# SiLabs2TC.net
KiCad netlist of a schematic drawn in EAGLE
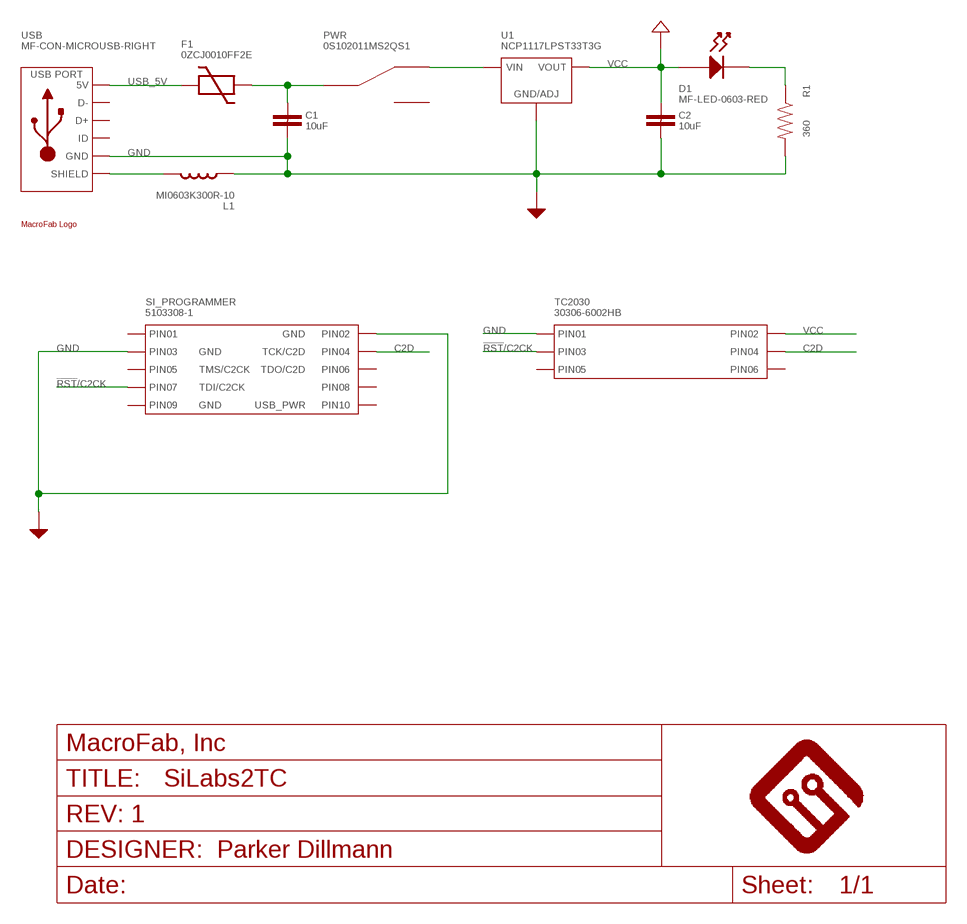
[diagram p0: schematic, sheet 1]

(export (version "E")
  (design (tool "Eeschema 10.0.6"))
  (components
    (comp (ref "C1")
      (value "10uF")
      (footprint "eagle-import:1206")
      (libsource (lib "eagle-import") (part "CAPACITOR_NON_POLAR_1206"))
    )
    (comp (ref "C2")
      (value "10uF")
      (footprint "eagle-import:1206")
      (libsource (lib "eagle-import") (part "CAPACITOR_NON_POLAR_1206"))
    )
    (comp (ref "D1")
      (value "MF-LED-0603-RED")
      (footprint "eagle-import:LED0805")
      (libsource (lib "eagle-import") (part "LED_SINGLE_0805"))
    )
    (comp (ref "F1")
      (value "0ZCJ0010FF2E")
      (footprint "eagle-import:1206")
      (libsource (lib "eagle-import") (part "PTC_FUSE_1206"))
    )
    (comp (ref "FRAME1")
      (value "MF_FRAMEDEFAULT")
      (footprint "eagle-import:MF_FRAME_DEFAULT")
      (fields (field (name "DNAME") "Parker Dillmann") (field (name "REVNUM") "REV: 1"))
      (libsource (lib "eagle-import") (part "MF_FRAMEDEFAULT"))
    )
    (comp (ref "L1")
      (value "MI0603K300R-10")
      (footprint "eagle-import:L0603")
      (libsource (lib "eagle-import") (part "INDUCTOR_0603"))
    )
    (comp (ref "PWR")
      (value "0S102011MS2QS1")
      (footprint "eagle-import:0S102011MS2QS1")
      (libsource (lib "eagle-import") (part "SPDT_0S102011MS2QS1"))
    )
    (comp (ref "R1")
      (value "360")
      (footprint "eagle-import:R0805")
      (libsource (lib "eagle-import") (part "RESISTOR_0805"))
    )
    (comp (ref "SI_PROGRAMMER")
      (value "5103308-1")
      (footprint "eagle-import:5103308-1")
      (fields
        (field (name "LABEL02") "GND")
        (field (name "LABEL03") "GND")
        (field (name "LABEL04") "TCK/C2D")
        (field (name "LABEL05") "TMS/C2CK")
        (field (name "LABEL06") "TDO/C2D")
        (field (name "LABEL07") "TDI/C2CK")
        (field (name "LABEL09") "GND")
        (field (name "LABEL10") "USB_PWR")
      )
      (libsource (lib "eagle-import") (part "CON_02X05_5103308-1"))
    )
    (comp (ref "TC2030")
      (value "30306-6002HB")
      (footprint "eagle-import:30306-6002HB")
      (libsource (lib "eagle-import") (part "CON_02X03_30306-6002HB"))
    )
    (comp (ref "U$3")
      (value "MF_LOGOLOGO_MEDIUM")
      (footprint "eagle-import:MF_LOGO_MEDIUM")
      (libsource (lib "eagle-import") (part "MF_LOGOLOGO_MEDIUM"))
    )
    (comp (ref "U1")
      (value "NCP1117LPST33T3G")
      (footprint "eagle-import:SOT-223-3")
      (libsource (lib "eagle-import") (part "NCP1117LPST33T3G"))
    )
    (comp (ref "USB")
      (value "MF-CON-MICROUSB-RIGHT")
      (footprint "eagle-import:MICROUSB-RIGHT")
      (libsource (lib "eagle-import") (part "USB_MICRO_RIGHT"))
    )
  )
  (nets
    (net (code "1") (name "/C2D") (class "Default")
      (node (ref "SI_PROGRAMMER") (pin "4") (pinfunction "PIN4_4") (pintype "bidirectional"))
      (node (ref "TC2030") (pin "4") (pinfunction "PIN4_4") (pintype "bidirectional"))
    )
    (net (code "2") (name "/USB_5V") (class "Default")
      (node (ref "F1") (pin "1") (pinfunction "P$1_1") (pintype "bidirectional"))
      (node (ref "USB") (pin "1") (pinfunction "5V_1") (pintype "power_in"))
    )
    (net (code "3") (name "/~{RST}{slash}C2CK") (class "Default")
      (node (ref "SI_PROGRAMMER") (pin "7") (pinfunction "PIN7_7") (pintype "bidirectional"))
      (node (ref "TC2030") (pin "3") (pinfunction "PIN3_3") (pintype "bidirectional"))
    )
    (net (code "4") (name "GND_RAIL") (class "Default")
      (node (ref "C1") (pin "2") (pinfunction "2_2") (pintype "passive"))
      (node (ref "C2") (pin "2") (pinfunction "2_2") (pintype "passive"))
      (node (ref "L1") (pin "P$1") (pinfunction "P$1_P$1") (pintype "passive"))
      (node (ref "R1") (pin "P$2") (pinfunction "P$2_P$2") (pintype "passive"))
      (node (ref "SI_PROGRAMMER") (pin "2") (pinfunction "PIN2_2") (pintype "bidirectional"))
      (node (ref "SI_PROGRAMMER") (pin "3") (pinfunction "PIN3_3") (pintype "bidirectional"))
      (node (ref "TC2030") (pin "1") (pinfunction "PIN1_1") (pintype "bidirectional"))
      (node (ref "U1") (pin "P$2") (pinfunction "GND/ADJ_P$2") (pintype "bidirectional"))
      (node (ref "USB") (pin "5") (pinfunction "GND_5") (pintype "power_in"))
    )
    (net (code "5") (name "Net-(D1-PadCATHODE)") (class "Default")
      (node (ref "D1") (pin "CATHODE") (pinfunction "CATHODE_CATHODE") (pintype "power_in"))
      (node (ref "R1") (pin "P$1") (pinfunction "P$1_P$1") (pintype "passive"))
    )
    (net (code "6") (name "Net-(F1-P$2)") (class "Default")
      (node (ref "C1") (pin "1") (pinfunction "1_1") (pintype "passive"))
      (node (ref "F1") (pin "2") (pinfunction "P$2_2") (pintype "bidirectional"))
      (node (ref "PWR") (pin "2") (pinfunction "C_2") (pintype "bidirectional"))
    )
    (net (code "7") (name "Net-(L1-PadP$2)") (class "Default")
      (node (ref "L1") (pin "P$2") (pinfunction "P$2_P$2") (pintype "passive"))
      (node (ref "USB") (pin "S1") (pinfunction "SLD_S1") (pintype "power_in"))
      (node (ref "USB") (pin "S2") (pinfunction "SLD_S2") (pintype "power_in"))
      (node (ref "USB") (pin "S3") (pinfunction "SLD_S3") (pintype "power_in"))
      (node (ref "USB") (pin "S4") (pinfunction "SLD_S4") (pintype "power_in"))
      (node (ref "USB") (pin "S5") (pinfunction "SLD_S5") (pintype "power_in"))
      (node (ref "USB") (pin "S6") (pinfunction "SLD_S6") (pintype "power_in"))
    )
    (net (code "8") (name "Net-(U1-VIN)") (class "Default")
      (node (ref "PWR") (pin "1") (pinfunction "1_1") (pintype "bidirectional"))
      (node (ref "U1") (pin "P$4") (pinfunction "VIN_P$4") (pintype "bidirectional"))
    )
    (net (code "9") (name "POWER_RAIL") (class "Default")
      (node (ref "C2") (pin "1") (pinfunction "1_1") (pintype "passive"))
      (node (ref "D1") (pin "ANODE") (pinfunction "ANODE_ANODE") (pintype "power_in"))
      (node (ref "TC2030") (pin "2") (pinfunction "PIN2_2") (pintype "bidirectional"))
      (node (ref "U1") (pin "P$1") (pinfunction "VOUT_P$1") (pintype "bidirectional"))
      (node (ref "U1") (pin "P$3") (pinfunction "VOUT_P$3") (pintype "bidirectional"))
    )
    (net (code "10") (name "unconnected-(PWR-2-Pad3)") (class "Default")
      (node (ref "PWR") (pin "3") (pinfunction "2_3") (pintype "bidirectional"))
    )
    (net (code "11") (name "unconnected-(SI_PROGRAMMER-PIN1-Pad1)") (class "Default")
      (node (ref "SI_PROGRAMMER") (pin "1") (pinfunction "PIN1_1") (pintype "bidirectional"))
    )
    (net (code "12") (name "unconnected-(SI_PROGRAMMER-PIN5-Pad5)") (class "Default")
      (node (ref "SI_PROGRAMMER") (pin "5") (pinfunction "PIN5_5") (pintype "bidirectional"))
    )
    (net (code "13") (name "unconnected-(SI_PROGRAMMER-PIN6-Pad6)") (class "Default")
      (node (ref "SI_PROGRAMMER") (pin "6") (pinfunction "PIN6_6") (pintype "bidirectional"))
    )
    (net (code "14") (name "unconnected-(SI_PROGRAMMER-PIN8-Pad8)") (class "Default")
      (node (ref "SI_PROGRAMMER") (pin "8") (pinfunction "PIN8_8") (pintype "bidirectional"))
    )
    (net (code "15") (name "unconnected-(SI_PROGRAMMER-PIN9-Pad9)") (class "Default")
      (node (ref "SI_PROGRAMMER") (pin "9") (pinfunction "PIN9_9") (pintype "bidirectional"))
    )
    (net (code "16") (name "unconnected-(SI_PROGRAMMER-PIN10-Pad10)") (class "Default")
      (node (ref "SI_PROGRAMMER") (pin "10") (pinfunction "PIN10_10") (pintype "bidirectional"))
    )
    (net (code "17") (name "unconnected-(TC2030-PIN5-Pad5)") (class "Default")
      (node (ref "TC2030") (pin "5") (pinfunction "PIN5_5") (pintype "bidirectional"))
    )
    (net (code "18") (name "unconnected-(TC2030-PIN6-Pad6)") (class "Default")
      (node (ref "TC2030") (pin "6") (pinfunction "PIN6_6") (pintype "bidirectional"))
    )
    (net (code "19") (name "unconnected-(USB-D+-Pad3)") (class "Default")
      (node (ref "USB") (pin "3") (pinfunction "D+_3") (pintype "bidirectional"))
    )
    (net (code "20") (name "unconnected-(USB-D--Pad2)") (class "Default")
      (node (ref "USB") (pin "2") (pinfunction "D-_2") (pintype "bidirectional"))
    )
    (net (code "21") (name "unconnected-(USB-ID-Pad4)") (class "Default")
      (node (ref "USB") (pin "4") (pinfunction "ID_4") (pintype "bidirectional"))
    )
  )
)
